# MainSheet.net
KiCad netlist of a schematic drawn in Altium Designer
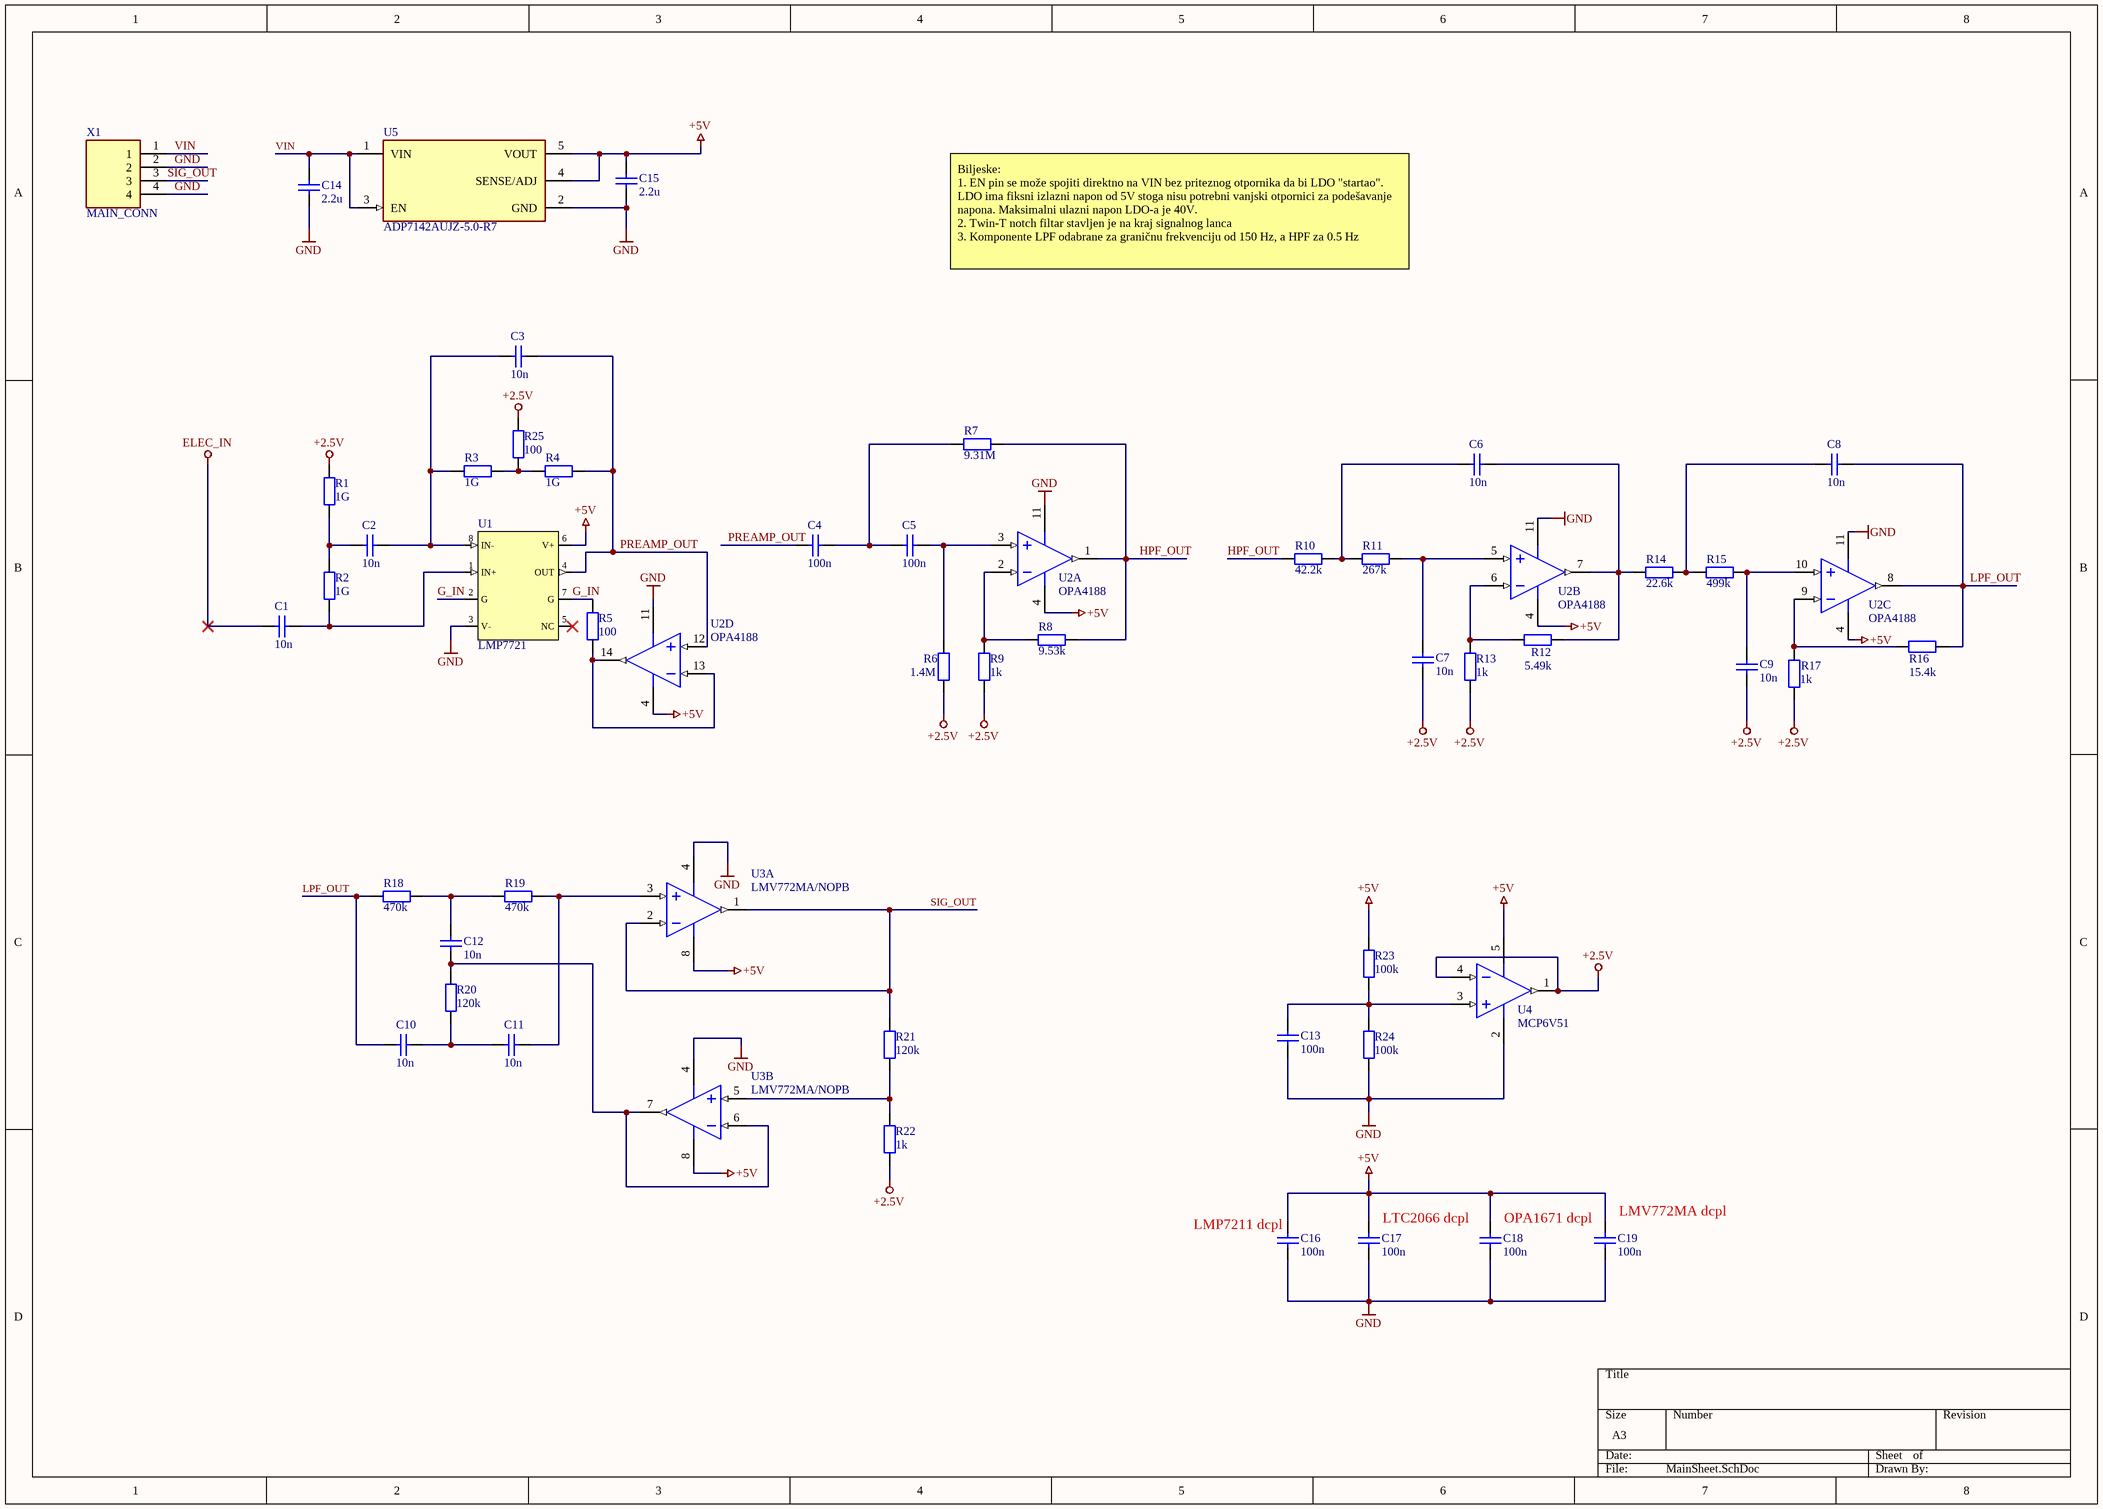
[diagram p0: MainSheet.SchDoc]

(export (version "E")
  (design (tool "Eeschema 10.0.6"))
  (components
    (comp (ref "C1")
      (value "10n")
      (footprint "CAP_0603")
      (description "C0603C103J3GACTU")
      (fields (field (name "PUBLISHER") "Altium Limited"))
      (libsource (lib "Miscellaneous Devices") (part "Cap"))
    )
    (comp (ref "C2")
      (value "10n")
      (footprint "CAP_0603")
      (description "C0603C103J3GACTU")
      (fields (field (name "PUBLISHER") "Altium Limited"))
      (libsource (lib "Miscellaneous Devices") (part "Cap"))
    )
    (comp (ref "C3")
      (value "10n")
      (footprint "CAP_0603")
      (description "C0603C103J3GACTU")
      (fields (field (name "PUBLISHER") "Altium Limited"))
      (libsource (lib "Miscellaneous Devices") (part "Cap"))
    )
    (comp (ref "C4")
      (value "100n")
      (footprint "CAPC3216X190")
      (description "Capacitor")
      (fields (field (name "PUBLISHER") "Altium Limited"))
      (libsource (lib "Miscellaneous Devices") (part "Cap"))
    )
    (comp (ref "C5")
      (value "100n")
      (footprint "CAPC3216X190")
      (description "Capacitor")
      (fields (field (name "PUBLISHER") "Altium Limited"))
      (libsource (lib "Miscellaneous Devices") (part "Cap"))
    )
    (comp (ref "C6")
      (value "10n")
      (footprint "CAP_0603")
      (description "Capacitor")
      (fields (field (name "PUBLISHER") "Altium Limited"))
      (libsource (lib "Miscellaneous Devices") (part "Cap"))
    )
    (comp (ref "C7")
      (value "10n")
      (footprint "CAP_0603")
      (description "Capacitor")
      (fields (field (name "PUBLISHER") "Altium Limited"))
      (libsource (lib "Miscellaneous Devices") (part "Cap"))
    )
    (comp (ref "C8")
      (value "10n")
      (footprint "CAP_0603")
      (description "Capacitor")
      (fields (field (name "PUBLISHER") "Altium Limited"))
      (libsource (lib "Miscellaneous Devices") (part "Cap"))
    )
    (comp (ref "C9")
      (value "10n")
      (footprint "CAP_0603")
      (description "Capacitor")
      (fields (field (name "PUBLISHER") "Altium Limited"))
      (libsource (lib "Miscellaneous Devices") (part "Cap"))
    )
    (comp (ref "C10")
      (value "10n")
      (footprint "CAP_0603")
      (description "Capacitor")
      (fields (field (name "PUBLISHER") "Altium Limited"))
      (libsource (lib "Miscellaneous Devices") (part "Cap"))
    )
    (comp (ref "C11")
      (value "10n")
      (footprint "CAP_0603")
      (description "Capacitor")
      (fields (field (name "PUBLISHER") "Altium Limited"))
      (libsource (lib "Miscellaneous Devices") (part "Cap"))
    )
    (comp (ref "C12")
      (value "10n")
      (footprint "CAP_0603")
      (description "Capacitor")
      (fields (field (name "PUBLISHER") "Altium Limited"))
      (libsource (lib "Miscellaneous Devices") (part "Cap"))
    )
    (comp (ref "C13")
      (value "100n")
      (footprint "CAP_0603")
      (description "MC0402B104K100CT")
      (libsource (lib "Miscellaneous Devices") (part "Cap"))
    )
    (comp (ref "C14")
      (value "2.2u")
      (footprint "CAP_0805")
      (description "Capacitor")
      (fields (field (name "PUBLISHER") "Altium Limited"))
      (libsource (lib "Miscellaneous Devices") (part "Cap"))
    )
    (comp (ref "C15")
      (value "2.2u")
      (footprint "CAP_0805")
      (description "Capacitor")
      (fields (field (name "PUBLISHER") "Altium Limited"))
      (libsource (lib "Miscellaneous Devices") (part "Cap"))
    )
    (comp (ref "C16")
      (value "100n")
      (footprint "CAP_0603")
      (description "MC0402B104K100CT")
      (fields (field (name "PUBLISHER") "Altium Limited"))
      (libsource (lib "Miscellaneous Devices") (part "Cap"))
    )
    (comp (ref "C17")
      (value "100n")
      (footprint "CAP_0603")
      (description "MC0402B104K100CT")
      (fields (field (name "PUBLISHER") "Altium Limited"))
      (libsource (lib "Miscellaneous Devices") (part "Cap"))
    )
    (comp (ref "C18")
      (value "100n")
      (footprint "CAP_0603")
      (description "MC0402B104K100CT")
      (fields (field (name "PUBLISHER") "Altium Limited"))
      (libsource (lib "Miscellaneous Devices") (part "Cap"))
    )
    (comp (ref "C19")
      (value "100n")
      (footprint "CAP_0603")
      (description "MC0402B104K100CT")
      (fields (field (name "PUBLISHER") "Altium Limited"))
      (libsource (lib "Miscellaneous Devices") (part "Cap"))
    )
    (comp (ref "R1")
      (value "1G")
      (footprint "RESC2012X60N")
      (description "HR0805F-1G0JI")
      (fields (field (name "PUBLISHER") "Altium Limited"))
      (libsource (lib "") (part "Res2_1"))
    )
    (comp (ref "R2")
      (value "1G")
      (footprint "RESC2012X60N")
      (description "HR0805F-1G0JI")
      (fields (field (name "PUBLISHER") "Altium Limited"))
      (libsource (lib "") (part "Res2_1"))
    )
    (comp (ref "R3")
      (value "1G")
      (footprint "RESC2012X60N")
      (description "HR0805F-1G0JI")
      (fields (field (name "PUBLISHER") "Altium Limited"))
      (libsource (lib "") (part "Res2_2"))
    )
    (comp (ref "R4")
      (value "1G")
      (footprint "RESC2012X60N")
      (description "HR0805F-1G0JI")
      (fields (field (name "PUBLISHER") "Altium Limited"))
      (libsource (lib "") (part "Res2_2"))
    )
    (comp (ref "R5")
      (value "100")
      (footprint "RES_0603")
      (description "CPF0402B100RE1")
      (fields (field (name "PUBLISHER") "Altium Limited"))
      (libsource (lib "Miscellaneous Devices") (part "Res2"))
    )
    (comp (ref "R6")
      (value "1.4M")
      (footprint "RES_0603")
      (description "Resistor")
      (fields (field (name "PUBLISHER") "Altium Limited"))
      (libsource (lib "") (part "Res2_2"))
    )
    (comp (ref "R7")
      (value "9.31M")
      (footprint "RES_0603")
      (description "Resistor")
      (fields (field (name "PUBLISHER") "Altium Limited"))
      (libsource (lib "") (part "Res2_3"))
    )
    (comp (ref "R8")
      (value "9.53k")
      (footprint "RES_0603")
      (description "Resistor")
      (fields (field (name "PUBLISHER") "Altium Limited"))
      (libsource (lib "") (part "Res2_1"))
    )
    (comp (ref "R9")
      (value "1k")
      (footprint "RES_0603")
      (description "Resistor")
      (fields (field (name "PUBLISHER") "Altium Limited"))
      (libsource (lib "") (part "Res2_2"))
    )
    (comp (ref "R10")
      (value "42.2k")
      (footprint "RES_0603")
      (description "Resistor")
      (fields (field (name "PUBLISHER") "Altium Limited"))
      (libsource (lib "") (part "Res2_3"))
    )
    (comp (ref "R11")
      (value "267k")
      (footprint "RES_0603")
      (description "Resistor")
      (fields (field (name "PUBLISHER") "Altium Limited"))
      (libsource (lib "") (part "Res2_3"))
    )
    (comp (ref "R12")
      (value "5.49k")
      (footprint "RES_0603")
      (description "Resistor")
      (fields (field (name "PUBLISHER") "Altium Limited"))
      (libsource (lib "") (part "Res2_1"))
    )
    (comp (ref "R13")
      (value "1k")
      (footprint "RES_0603")
      (description "Resistor")
      (fields (field (name "PUBLISHER") "Altium Limited"))
      (libsource (lib "Miscellaneous Devices") (part "Res2"))
    )
    (comp (ref "R14")
      (value "22.6k")
      (footprint "RES_0603")
      (description "Resistor")
      (fields (field (name "PUBLISHER") "Altium Limited"))
      (libsource (lib "") (part "Res2_3"))
    )
    (comp (ref "R15")
      (value "499k")
      (footprint "RES_0603")
      (description "Resistor")
      (fields (field (name "PUBLISHER") "Altium Limited"))
      (libsource (lib "") (part "Res2_3"))
    )
    (comp (ref "R16")
      (value "15.4k")
      (footprint "RES_0603")
      (description "Resistor")
      (fields (field (name "PUBLISHER") "Altium Limited"))
      (libsource (lib "") (part "Res2_1"))
    )
    (comp (ref "R17")
      (value "1k")
      (footprint "RES_0603")
      (description "Resistor")
      (fields (field (name "PUBLISHER") "Altium Limited"))
      (libsource (lib "Miscellaneous Devices") (part "Res2"))
    )
    (comp (ref "R18")
      (value "470k")
      (footprint "RES_0603")
      (description "Resistor")
      (fields (field (name "PUBLISHER") "Altium Limited"))
      (libsource (lib "") (part "Res2_3"))
    )
    (comp (ref "R19")
      (value "470k")
      (footprint "RES_0603")
      (description "Resistor")
      (fields (field (name "PUBLISHER") "Altium Limited"))
      (libsource (lib "") (part "Res2_3"))
    )
    (comp (ref "R20")
      (value "120k")
      (footprint "RES_0603")
      (description "Resistor")
      (fields (field (name "PUBLISHER") "Altium Limited"))
      (libsource (lib "") (part "Res2_2"))
    )
    (comp (ref "R21")
      (value "120k")
      (footprint "RES_0603")
      (description "Resistor")
      (fields (field (name "PUBLISHER") "Altium Limited"))
      (libsource (lib "") (part "Res2_2"))
    )
    (comp (ref "R22")
      (value "1k")
      (footprint "RES_0603")
      (description "Resistor")
      (fields (field (name "PUBLISHER") "Altium Limited"))
      (libsource (lib "") (part "Res2_2"))
    )
    (comp (ref "R23")
      (value "100k")
      (footprint "RES_0603")
      (description "MCS04020C1003FE000")
      (libsource (lib "Miscellaneous Devices") (part "Res2"))
    )
    (comp (ref "R24")
      (value "100k")
      (footprint "RES_0603")
      (description "MCS04020C1003FE000")
      (libsource (lib "Miscellaneous Devices") (part "Res2"))
    )
    (comp (ref "R25")
      (value "100")
      (footprint "RES_0603")
      (description "CPF0402B100RE1")
      (fields (field (name "PUBLISHER") "Altium Limited"))
      (libsource (lib "") (part "Res2_2"))
    )
    (comp (ref "U1")
      (value "LMP7721")
      (footprint "SOIC127P600X175-8N")
      (description "LMP7721 3-Femtoampere Input Bias Current Precision Amplifier")
      (libsource (lib "SymolLib") (part "LMP7721"))
    )
    (comp (ref "U2")
      (value "OPA4188")
      (footprint "SOP65P640X120-14N")
      (description "Quad Channel Operational Amplifier, 4 MHz BW, 20 V/us SR, Industrial, 14-pin DIP (Q-14), Tube")
      (fields (field (name "GENERIC PART NUMBER") "AD713") (field (name "MANUFACTURER") "Analog Devices"))
      (libsource (lib "Analog Devices Operational Amplifiers") (part "AD713AQ"))
    )
    (comp (ref "U3")
      (value "LMV772MA/NOPB")
      (footprint "D0008A_M")
      (description "Dual, Low Offset, Low Noise, RRO Operational Amplifier, 8-pin Narrow SOIC, Pb-Free, 95 Rail")
      (fields (field (name "MANUFACTURER") "Texas Instruments"))
      (libsource (lib "Altium Content Vault") (part "AMP-OPA-LM6132-8"))
    )
    (comp (ref "U4")
      (value "MCP6V51")
      (footprint "SOT95P280X145-5N")
      (description "MCP6V51T-E/OT")
      (libsource (lib "TI Amplifiers and Linear Operational Amplifier Precision Amplifier Part One") (part "OPA336NJ/250"))
    )
    (comp (ref "U5")
      (value "ADP7142AUJZ-5.0-R7")
      (footprint "FP-UJ-5-IPC_B")
      (description "IC REG LINEAR 5V 200MA TSOT23-5")
      (libsource (lib "Altium Content Vault") (part "4a7971eea0f250dff842508c33254cb"))
    )
    (comp (ref "X1")
      (value "MAIN_CONN")
      (footprint "SamacSys:SHDRRA4W50P15X200_1X4_1000X770X525P")
      (description "Connector")
      (fields
        (field (name "MOUSER2 PART NUMBER") "571-440055-4")
        (field (name "MANUFACTURER_PART_NUMBER") "440055-4")
      )
      (libsource (lib "SamacSys") (part "440055-4"))
    )
  )
  (nets
    (net (code "1") (name "+2.5V") (class "Default")
      (node (ref "C7") (pin "1") (pinfunction "1_1") (pintype "passive"))
      (node (ref "C9") (pin "1") (pinfunction "1_1") (pintype "passive"))
      (node (ref "R1") (pin "1") (pinfunction "1_1") (pintype "passive"))
      (node (ref "R13") (pin "2") (pinfunction "2_2") (pintype "passive"))
      (node (ref "R17") (pin "2") (pinfunction "2_2") (pintype "passive"))
      (node (ref "R22") (pin "1") (pinfunction "1_1") (pintype "passive"))
      (node (ref "R25") (pin "2") (pinfunction "2_2") (pintype "passive"))
      (node (ref "R6") (pin "1") (pinfunction "1_1") (pintype "passive"))
      (node (ref "R9") (pin "1") (pinfunction "1_1") (pintype "passive"))
      (node (ref "U4") (pin "1") (pinfunction "OUT_1") (pintype "output"))
      (node (ref "U4") (pin "4") (pinfunction "IN-_4") (pintype "input"))
    )
    (net (code "2") (name "+5V") (class "Default")
      (node (ref "C15") (pin "1") (pinfunction "1_1") (pintype "passive"))
      (node (ref "C16") (pin "2") (pinfunction "2_2") (pintype "passive"))
      (node (ref "C17") (pin "2") (pinfunction "2_2") (pintype "passive"))
      (node (ref "C18") (pin "2") (pinfunction "2_2") (pintype "passive"))
      (node (ref "C19") (pin "2") (pinfunction "2_2") (pintype "passive"))
      (node (ref "R23") (pin "1") (pinfunction "1_1") (pintype "passive"))
      (node (ref "U1") (pin "6") (pinfunction "V+_6") (pintype "power_in"))
      (node (ref "U2") (pin "4") (pinfunction "+VS_4") (pintype "power_in"))
      (node (ref "U3") (pin "8") (pinfunction "V+_8") (pintype "power_in"))
      (node (ref "U4") (pin "5") (pinfunction "V+_5") (pintype "power_in"))
      (node (ref "U5") (pin "4") (pinfunction "SENSE/ADJ_4") (pintype "passive"))
      (node (ref "U5") (pin "5") (pinfunction "VOUT_5") (pintype "power_in"))
    )
    (net (code "3") (name "/G_IN") (class "Default")
      (node (ref "R5") (pin "1") (pinfunction "1_1") (pintype "passive"))
      (node (ref "U1") (pin "2") (pinfunction "G_2") (pintype "passive"))
      (node (ref "U1") (pin "7") (pinfunction "G_7") (pintype "passive"))
    )
    (net (code "4") (name "/HPF_OUT") (class "Default")
      (node (ref "R10") (pin "1") (pinfunction "1_1") (pintype "passive"))
      (node (ref "R7") (pin "2") (pinfunction "2_2") (pintype "passive"))
      (node (ref "R8") (pin "1") (pinfunction "1_1") (pintype "passive"))
      (node (ref "U2") (pin "1") (pinfunction "OUT_1_1") (pintype "output"))
    )
    (net (code "5") (name "/LPF_OUT") (class "Default")
      (node (ref "C10") (pin "2") (pinfunction "2_2") (pintype "passive"))
      (node (ref "C8") (pin "1") (pinfunction "1_1") (pintype "passive"))
      (node (ref "R16") (pin "1") (pinfunction "1_1") (pintype "passive"))
      (node (ref "R18") (pin "1") (pinfunction "1_1") (pintype "passive"))
      (node (ref "U2") (pin "8") (pinfunction "OUT_3_8") (pintype "output"))
    )
    (net (code "6") (name "/PREAMP_OUT") (class "Default")
      (node (ref "C3") (pin "2") (pinfunction "2_2") (pintype "passive"))
      (node (ref "C4") (pin "1") (pinfunction "1_1") (pintype "passive"))
      (node (ref "R4") (pin "2") (pinfunction "2_2") (pintype "passive"))
      (node (ref "U1") (pin "4") (pinfunction "OUT_4") (pintype "output"))
      (node (ref "U2") (pin "12") (pinfunction "+IN_4_12") (pintype "input"))
    )
    (net (code "7") (name "/SIG_OUT") (class "Default")
      (node (ref "R21") (pin "2") (pinfunction "2_2") (pintype "passive"))
      (node (ref "U3") (pin "1") (pinfunction "OUTA_1") (pintype "output"))
      (node (ref "U3") (pin "2") (pinfunction "INA-_2") (pintype "input"))
      (node (ref "X1") (pin "3") (pinfunction "3_3") (pintype "passive"))
    )
    (net (code "8") (name "/VIN") (class "Default")
      (node (ref "C14") (pin "1") (pinfunction "1_1") (pintype "passive"))
      (node (ref "U5") (pin "1") (pinfunction "VIN_1") (pintype "power_in"))
      (node (ref "U5") (pin "3") (pinfunction "EN_3") (pintype "input"))
      (node (ref "X1") (pin "1") (pinfunction "1_1") (pintype "passive"))
    )
    (net (code "9") (name "ELEC_IN") (class "Default")
      (node (ref "C1") (pin "1") (pinfunction "1_1") (pintype "passive"))
    )
    (net (code "10") (name "GND") (class "Default")
      (node (ref "C13") (pin "1") (pinfunction "1_1") (pintype "passive"))
      (node (ref "C14") (pin "2") (pinfunction "2_2") (pintype "passive"))
      (node (ref "C15") (pin "2") (pinfunction "2_2") (pintype "passive"))
      (node (ref "C16") (pin "1") (pinfunction "1_1") (pintype "passive"))
      (node (ref "C17") (pin "1") (pinfunction "1_1") (pintype "passive"))
      (node (ref "C18") (pin "1") (pinfunction "1_1") (pintype "passive"))
      (node (ref "C19") (pin "1") (pinfunction "1_1") (pintype "passive"))
      (node (ref "R24") (pin "2") (pinfunction "2_2") (pintype "passive"))
      (node (ref "U1") (pin "3") (pinfunction "V-_3") (pintype "power_in"))
      (node (ref "U2") (pin "11") (pinfunction "-VS_11") (pintype "power_in"))
      (node (ref "U3") (pin "4") (pinfunction "V-_4") (pintype "power_in"))
      (node (ref "U4") (pin "2") (pinfunction "V-_2") (pintype "power_in"))
      (node (ref "U5") (pin "2") (pinfunction "GND_2") (pintype "power_in"))
      (node (ref "X1") (pin "2") (pinfunction "2_2") (pintype "passive"))
      (node (ref "X1") (pin "4") (pinfunction "4_4") (pintype "passive"))
    )
    (net (code "11") (name "Net-(C2-Pad1)") (class "Default")
      (node (ref "C2") (pin "1") (pinfunction "1_1") (pintype "passive"))
      (node (ref "R1") (pin "2") (pinfunction "2_2") (pintype "passive"))
      (node (ref "R2") (pin "1") (pinfunction "1_1") (pintype "passive"))
    )
    (net (code "12") (name "Net-(C4-Pad2)") (class "Default")
      (node (ref "C4") (pin "2") (pinfunction "2_2") (pintype "passive"))
      (node (ref "C5") (pin "1") (pinfunction "1_1") (pintype "passive"))
      (node (ref "R7") (pin "1") (pinfunction "1_1") (pintype "passive"))
    )
    (net (code "13") (name "Net-(C6-Pad2)") (class "Default")
      (node (ref "C6") (pin "2") (pinfunction "2_2") (pintype "passive"))
      (node (ref "R10") (pin "2") (pinfunction "2_2") (pintype "passive"))
      (node (ref "R11") (pin "1") (pinfunction "1_1") (pintype "passive"))
    )
    (net (code "14") (name "Net-(C8-Pad2)") (class "Default")
      (node (ref "C8") (pin "2") (pinfunction "2_2") (pintype "passive"))
      (node (ref "R14") (pin "2") (pinfunction "2_2") (pintype "passive"))
      (node (ref "R15") (pin "1") (pinfunction "1_1") (pintype "passive"))
    )
    (net (code "15") (name "Net-(C10-Pad1)") (class "Default")
      (node (ref "C10") (pin "1") (pinfunction "1_1") (pintype "passive"))
      (node (ref "C11") (pin "2") (pinfunction "2_2") (pintype "passive"))
      (node (ref "R20") (pin "1") (pinfunction "1_1") (pintype "passive"))
    )
    (net (code "16") (name "Net-(C12-Pad2)") (class "Default")
      (node (ref "C12") (pin "2") (pinfunction "2_2") (pintype "passive"))
      (node (ref "R18") (pin "2") (pinfunction "2_2") (pintype "passive"))
      (node (ref "R19") (pin "1") (pinfunction "1_1") (pintype "passive"))
    )
    (net (code "17") (name "Net-(R25-Pad1)") (class "Default")
      (node (ref "R25") (pin "1") (pinfunction "1_1") (pintype "passive"))
      (node (ref "R3") (pin "2") (pinfunction "2_2") (pintype "passive"))
      (node (ref "R4") (pin "1") (pinfunction "1_1") (pintype "passive"))
    )
    (net (code "18") (name "Net-(U1-IN+)") (class "Default")
      (node (ref "C1") (pin "2") (pinfunction "2_2") (pintype "passive"))
      (node (ref "R2") (pin "2") (pinfunction "2_2") (pintype "passive"))
      (node (ref "U1") (pin "1") (pinfunction "IN+_1") (pintype "input"))
    )
    (net (code "19") (name "Net-(U1-IN-)") (class "Default")
      (node (ref "C2") (pin "2") (pinfunction "2_2") (pintype "passive"))
      (node (ref "C3") (pin "1") (pinfunction "1_1") (pintype "passive"))
      (node (ref "R3") (pin "1") (pinfunction "1_1") (pintype "passive"))
      (node (ref "U1") (pin "8") (pinfunction "IN-_8") (pintype "input"))
    )
    (net (code "20") (name "Net-(U2A-+IN_1)") (class "Default")
      (node (ref "C5") (pin "2") (pinfunction "2_2") (pintype "passive"))
      (node (ref "R6") (pin "2") (pinfunction "2_2") (pintype "passive"))
      (node (ref "U2") (pin "3") (pinfunction "+IN_1_3") (pintype "input"))
    )
    (net (code "21") (name "Net-(U2A--IN_1)") (class "Default")
      (node (ref "R8") (pin "2") (pinfunction "2_2") (pintype "passive"))
      (node (ref "R9") (pin "2") (pinfunction "2_2") (pintype "passive"))
      (node (ref "U2") (pin "2") (pinfunction "-IN_1_2") (pintype "input"))
    )
    (net (code "22") (name "Net-(U2B-+IN_2)") (class "Default")
      (node (ref "C7") (pin "2") (pinfunction "2_2") (pintype "passive"))
      (node (ref "R11") (pin "2") (pinfunction "2_2") (pintype "passive"))
      (node (ref "U2") (pin "5") (pinfunction "+IN_2_5") (pintype "input"))
    )
    (net (code "23") (name "Net-(U2B--IN_2)") (class "Default")
      (node (ref "R12") (pin "2") (pinfunction "2_2") (pintype "passive"))
      (node (ref "R13") (pin "1") (pinfunction "1_1") (pintype "passive"))
      (node (ref "U2") (pin "6") (pinfunction "-IN_2_6") (pintype "input"))
    )
    (net (code "24") (name "Net-(U2B-OUT_2)") (class "Default")
      (node (ref "C6") (pin "1") (pinfunction "1_1") (pintype "passive"))
      (node (ref "R12") (pin "1") (pinfunction "1_1") (pintype "passive"))
      (node (ref "R14") (pin "1") (pinfunction "1_1") (pintype "passive"))
      (node (ref "U2") (pin "7") (pinfunction "OUT_2_7") (pintype "output"))
    )
    (net (code "25") (name "Net-(U2C-+IN_3)") (class "Default")
      (node (ref "C9") (pin "2") (pinfunction "2_2") (pintype "passive"))
      (node (ref "R15") (pin "2") (pinfunction "2_2") (pintype "passive"))
      (node (ref "U2") (pin "10") (pinfunction "+IN_3_10") (pintype "input"))
    )
    (net (code "26") (name "Net-(U2C--IN_3)") (class "Default")
      (node (ref "R16") (pin "2") (pinfunction "2_2") (pintype "passive"))
      (node (ref "R17") (pin "1") (pinfunction "1_1") (pintype "passive"))
      (node (ref "U2") (pin "9") (pinfunction "-IN_3_9") (pintype "input"))
    )
    (net (code "27") (name "Net-(U2D--IN_4)") (class "Default")
      (node (ref "R5") (pin "2") (pinfunction "2_2") (pintype "passive"))
      (node (ref "U2") (pin "13") (pinfunction "-IN_4_13") (pintype "input"))
      (node (ref "U2") (pin "14") (pinfunction "OUT_4_14") (pintype "output"))
    )
    (net (code "28") (name "Net-(U3A-INA+)") (class "Default")
      (node (ref "C11") (pin "1") (pinfunction "1_1") (pintype "passive"))
      (node (ref "R19") (pin "2") (pinfunction "2_2") (pintype "passive"))
      (node (ref "U3") (pin "3") (pinfunction "INA+_3") (pintype "input"))
    )
    (net (code "29") (name "Net-(U3B-INB+)") (class "Default")
      (node (ref "R21") (pin "1") (pinfunction "1_1") (pintype "passive"))
      (node (ref "R22") (pin "2") (pinfunction "2_2") (pintype "passive"))
      (node (ref "U3") (pin "5") (pinfunction "INB+_5") (pintype "input"))
    )
    (net (code "30") (name "Net-(U3B-INB-)") (class "Default")
      (node (ref "C12") (pin "1") (pinfunction "1_1") (pintype "passive"))
      (node (ref "R20") (pin "2") (pinfunction "2_2") (pintype "passive"))
      (node (ref "U3") (pin "6") (pinfunction "INB-_6") (pintype "input"))
      (node (ref "U3") (pin "7") (pinfunction "OUTB_7") (pintype "output"))
    )
    (net (code "31") (name "Net-(U4-IN+)") (class "Default")
      (node (ref "C13") (pin "2") (pinfunction "2_2") (pintype "passive"))
      (node (ref "R23") (pin "2") (pinfunction "2_2") (pintype "passive"))
      (node (ref "R24") (pin "1") (pinfunction "1_1") (pintype "passive"))
      (node (ref "U4") (pin "3") (pinfunction "IN+_3") (pintype "input"))
    )
    (net (code "32") (name "unconnected-(U1-NC-Pad5)") (class "Default")
      (node (ref "U1") (pin "5") (pinfunction "NC_5") (pintype "passive+no_connect"))
    )
  )
)
